# MCChipProto.net
KiCad netlist of a schematic drawn in EAGLE
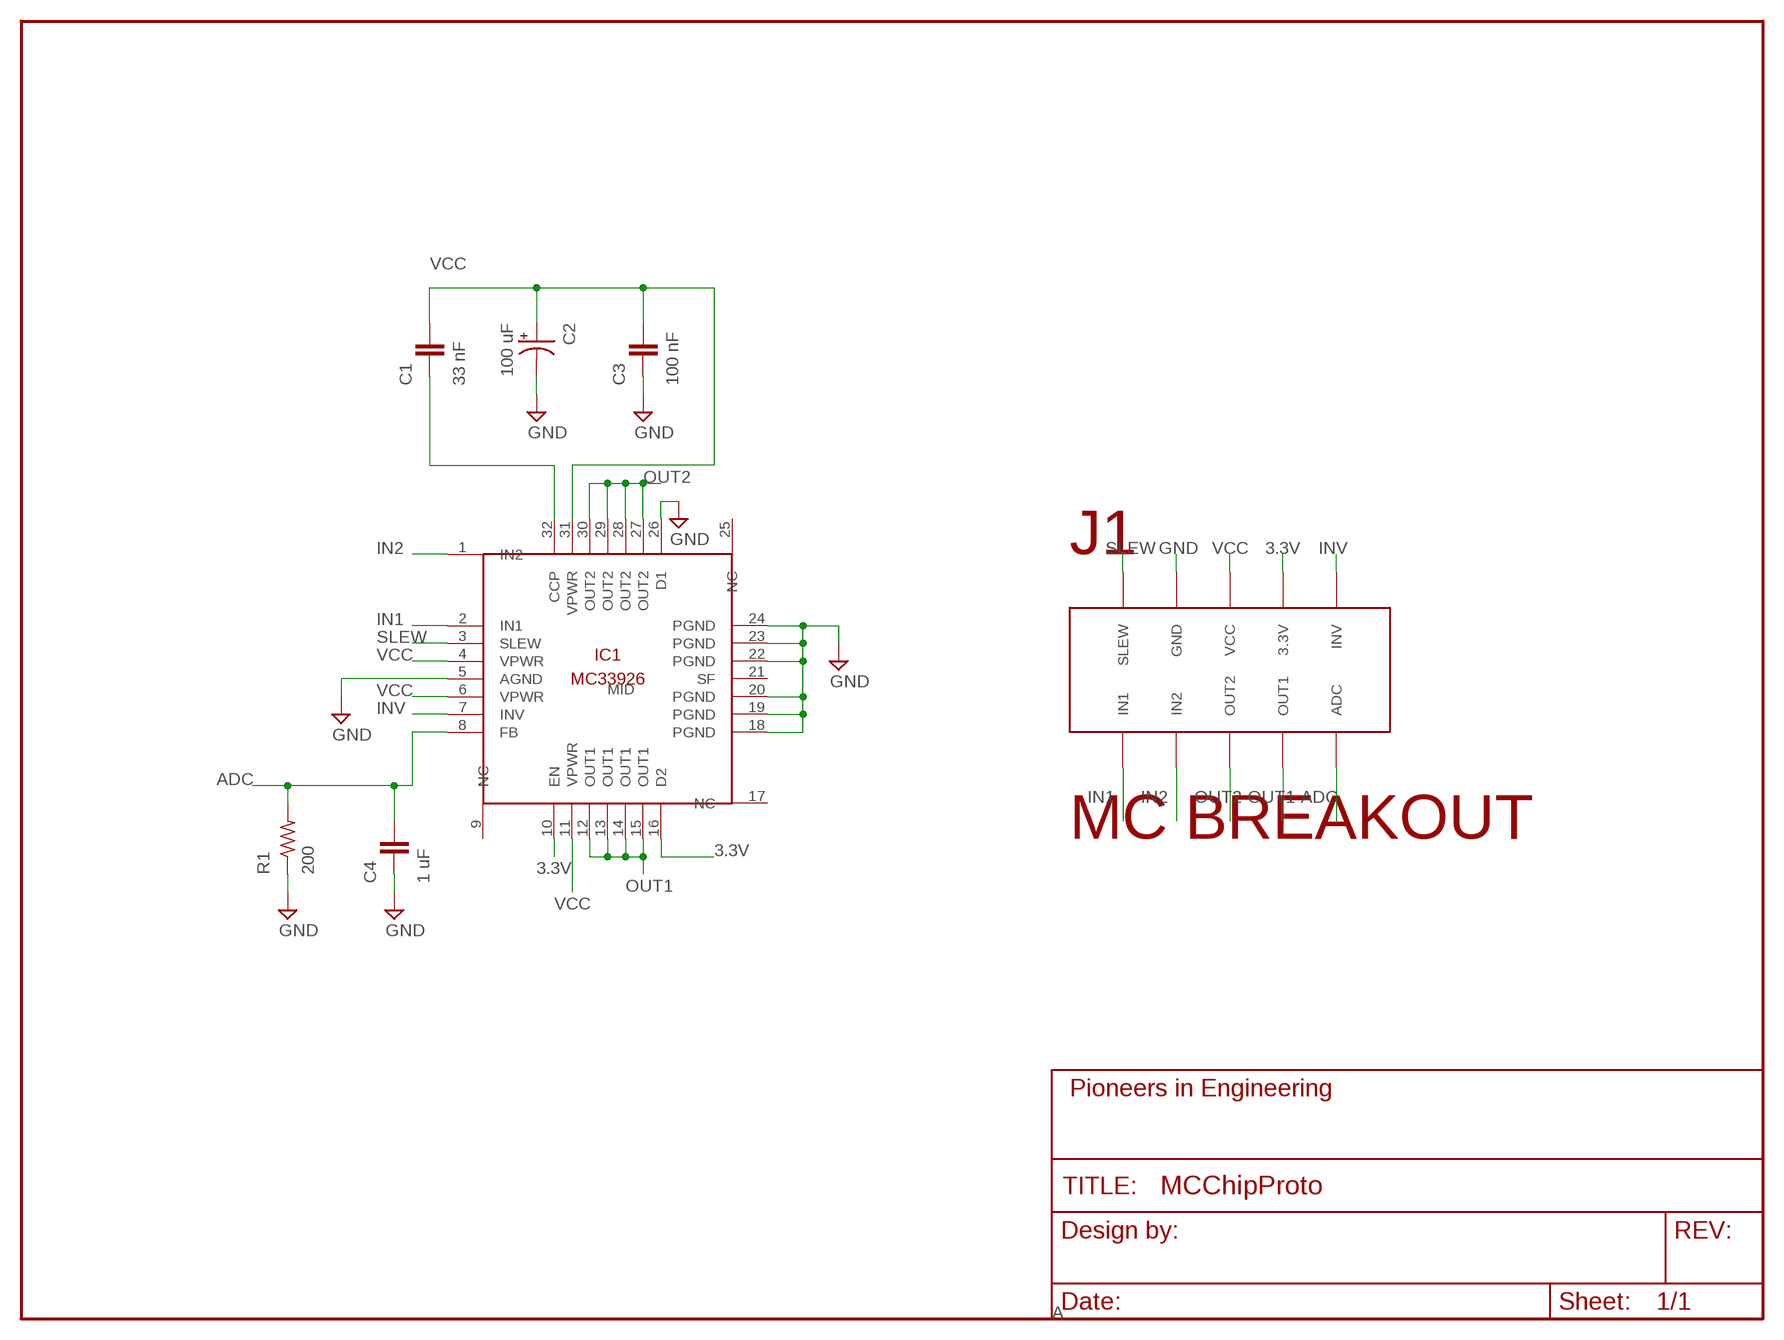
[diagram p0: schematic, sheet 1]

(export (version "E")
  (design (tool "Eeschema 10.0.6"))
  (components
    (comp (ref "C1")
      (value "33 nF")
      (footprint "eagle-import:0603-CAP")
      (libsource (lib "eagle-import") (part "CAP0603-CAP"))
    )
    (comp (ref "C2")
      (value "100 uF")
      (footprint "eagle-import:.248_CAP_THRU")
      (libsource (lib "eagle-import") (part "CAP_POLRADIAL"))
    )
    (comp (ref "C3")
      (value "100 nF")
      (footprint "eagle-import:0603-CAP")
      (libsource (lib "eagle-import") (part "CAP0603-CAP"))
    )
    (comp (ref "C4")
      (value "1 uF")
      (footprint "eagle-import:0603-CAP")
      (libsource (lib "eagle-import") (part "CAP0603-CAP"))
    )
    (comp (ref "IC1")
      (value "MC33926")
      (footprint "eagle-import:PQFN-32")
      (libsource (lib "eagle-import") (part "MC33926"))
    )
    (comp (ref "J1")
      (value "MC BREAKOUT")
      (footprint "eagle-import:2X5PIN")
      (libsource (lib "eagle-import") (part "2X5PIN"))
    )
    (comp (ref "R1")
      (value "200")
      (footprint "eagle-import:R0603")
      (fields (field (name "MANUFACTURER") "Rohm Semiconductor"))
      (libsource (lib "eagle-import") (part "R-US_R0603"))
    )
  )
  (nets
    (net (code "1") (name "/3.3V") (class "Default")
      (node (ref "IC1") (pin "10") (pinfunction "EN_10") (pintype "bidirectional"))
      (node (ref "IC1") (pin "16") (pinfunction "D2_16") (pintype "bidirectional"))
      (node (ref "J1") (pin "3.3V") (pinfunction "3.3V_3.3V") (pintype "bidirectional"))
    )
    (net (code "2") (name "/ADC") (class "Default")
      (node (ref "C4") (pin "2") (pinfunction "2_2") (pintype "passive"))
      (node (ref "IC1") (pin "8") (pinfunction "FB_8") (pintype "bidirectional"))
      (node (ref "J1") (pin "ADC") (pinfunction "ADC_ADC") (pintype "bidirectional"))
      (node (ref "R1") (pin "2") (pinfunction "2_2") (pintype "passive"))
    )
    (net (code "3") (name "/IN1") (class "Default")
      (node (ref "IC1") (pin "2") (pinfunction "IN1_2") (pintype "bidirectional"))
      (node (ref "J1") (pin "IN1") (pinfunction "IN1_IN1") (pintype "bidirectional"))
    )
    (net (code "4") (name "/IN2") (class "Default")
      (node (ref "IC1") (pin "1") (pinfunction "IN2_1") (pintype "bidirectional"))
      (node (ref "J1") (pin "IN2") (pinfunction "IN2_IN2") (pintype "bidirectional"))
    )
    (net (code "5") (name "/INV") (class "Default")
      (node (ref "IC1") (pin "7") (pinfunction "INV_7") (pintype "bidirectional"))
      (node (ref "J1") (pin "INV") (pinfunction "INV_INV") (pintype "bidirectional"))
    )
    (net (code "6") (name "/OUT1") (class "Default")
      (node (ref "IC1") (pin "12") (pinfunction "OUT1_12") (pintype "bidirectional"))
      (node (ref "IC1") (pin "13") (pinfunction "OUT1_13") (pintype "bidirectional"))
      (node (ref "IC1") (pin "14") (pinfunction "OUT1_14") (pintype "bidirectional"))
      (node (ref "IC1") (pin "15") (pinfunction "OUT1_15") (pintype "bidirectional"))
      (node (ref "J1") (pin "OUT1") (pinfunction "OUT1_OUT1") (pintype "bidirectional"))
    )
    (net (code "7") (name "/OUT2") (class "Default")
      (node (ref "IC1") (pin "27") (pinfunction "OUT2_27") (pintype "bidirectional"))
      (node (ref "IC1") (pin "28") (pinfunction "OUT2_28") (pintype "bidirectional"))
      (node (ref "IC1") (pin "29") (pinfunction "OUT2_29") (pintype "bidirectional"))
      (node (ref "IC1") (pin "30") (pinfunction "OUT2_30") (pintype "bidirectional"))
      (node (ref "J1") (pin "OUT2") (pinfunction "OUT2_OUT2") (pintype "bidirectional"))
    )
    (net (code "8") (name "/SLEW") (class "Default")
      (node (ref "IC1") (pin "3") (pinfunction "SLEW_3") (pintype "bidirectional"))
      (node (ref "J1") (pin "SLEW") (pinfunction "SLEW_SLEW") (pintype "bidirectional"))
    )
    (net (code "9") (name "/VCC") (class "Default")
      (node (ref "C1") (pin "2") (pinfunction "2_2") (pintype "passive"))
      (node (ref "C2") (pin "PLUS") (pinfunction "+_PLUS") (pintype "passive"))
      (node (ref "C3") (pin "2") (pinfunction "2_2") (pintype "passive"))
      (node (ref "IC1") (pin "11") (pinfunction "VPWR_11") (pintype "bidirectional"))
      (node (ref "IC1") (pin "31") (pinfunction "VPWR_31") (pintype "bidirectional"))
      (node (ref "IC1") (pin "4") (pinfunction "VPWR_4") (pintype "bidirectional"))
      (node (ref "IC1") (pin "6") (pinfunction "VPWR_6") (pintype "bidirectional"))
      (node (ref "J1") (pin "VCC") (pinfunction "VCC_VCC") (pintype "bidirectional"))
    )
    (net (code "10") (name "GND") (class "Default")
      (node (ref "C2") (pin "MINUS") (pinfunction "-_MINUS") (pintype "passive"))
      (node (ref "C3") (pin "1") (pinfunction "1_1") (pintype "passive"))
      (node (ref "C4") (pin "1") (pinfunction "1_1") (pintype "passive"))
      (node (ref "IC1") (pin "18") (pinfunction "PGND_18") (pintype "bidirectional"))
      (node (ref "IC1") (pin "19") (pinfunction "PGND_19") (pintype "bidirectional"))
      (node (ref "IC1") (pin "20") (pinfunction "PGND_20") (pintype "bidirectional"))
      (node (ref "IC1") (pin "22") (pinfunction "PGND_22") (pintype "bidirectional"))
      (node (ref "IC1") (pin "23") (pinfunction "PGND_23") (pintype "bidirectional"))
      (node (ref "IC1") (pin "24") (pinfunction "PGND_24") (pintype "bidirectional"))
      (node (ref "IC1") (pin "26") (pinfunction "D1_26") (pintype "bidirectional"))
      (node (ref "IC1") (pin "5") (pinfunction "AGND_5") (pintype "bidirectional"))
      (node (ref "J1") (pin "GND") (pinfunction "GND_GND") (pintype "bidirectional"))
      (node (ref "R1") (pin "1") (pinfunction "1_1") (pintype "passive"))
    )
    (net (code "11") (name "Net-(IC1-CCP)") (class "Default")
      (node (ref "C1") (pin "1") (pinfunction "1_1") (pintype "passive"))
      (node (ref "IC1") (pin "32") (pinfunction "CCP_32") (pintype "bidirectional"))
    )
    (net (code "12") (name "unconnected-(IC1-AGND-PadMID)") (class "Default")
      (node (ref "IC1") (pin "MID") (pinfunction "AGND_MID") (pintype "bidirectional"))
    )
    (net (code "13") (name "unconnected-(IC1-NC-Pad9)") (class "Default")
      (node (ref "IC1") (pin "9") (pinfunction "NC_9") (pintype "bidirectional"))
    )
    (net (code "14") (name "unconnected-(IC1-NC-Pad17)") (class "Default")
      (node (ref "IC1") (pin "17") (pinfunction "NC_17") (pintype "bidirectional"))
    )
    (net (code "15") (name "unconnected-(IC1-NC-Pad25)") (class "Default")
      (node (ref "IC1") (pin "25") (pinfunction "NC_25") (pintype "bidirectional"))
    )
    (net (code "16") (name "unconnected-(IC1-SF-Pad21)") (class "Default")
      (node (ref "IC1") (pin "21") (pinfunction "SF_21") (pintype "bidirectional"))
    )
  )
)
